# sensors.net
KiCad netlist of a schematic drawn in EAGLE
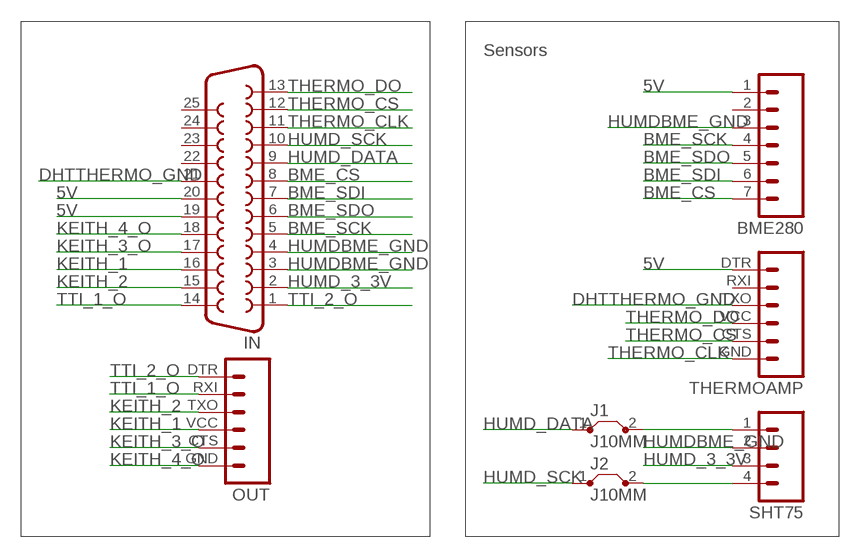
[diagram p0: schematic, sheet 1]

(export (version "E")
  (design (tool "Eeschema 10.0.6"))
  (components
    (comp (ref "BME280")
      (value "M07")
      (footprint "eagle-import:1X07")
      (libsource (lib "eagle-import") (part "M07"))
    )
    (comp (ref "IN")
      (value "F25HP")
      (footprint "eagle-import:F25HP")
      (libsource (lib "eagle-import") (part "F25HP"))
    )
    (comp (ref "J1")
      (value "J10MM")
      (footprint "eagle-import:10")
      (libsource (lib "eagle-import") (part "J10MM"))
    )
    (comp (ref "J2")
      (value "J10MM")
      (footprint "eagle-import:10")
      (libsource (lib "eagle-import") (part "J10MM"))
    )
    (comp (ref "OUT")
      (value "M06SIP")
      (footprint "eagle-import:1X06")
      (libsource (lib "eagle-import") (part "M06SIP"))
    )
    (comp (ref "SHT75")
      (value "M04SMD_LONG")
      (footprint "eagle-import:1X04-SMD_LONG")
      (libsource (lib "eagle-import") (part "M04SMD_LONG"))
    )
    (comp (ref "THERMOAMP")
      (value "M06SIP")
      (footprint "eagle-import:1X06")
      (libsource (lib "eagle-import") (part "M06SIP"))
    )
  )
  (nets
    (net (code "1") (name "/5V") (class "Default")
      (node (ref "BME280") (pin "1") (pinfunction "1_1") (pintype "passive"))
      (node (ref "IN") (pin "19") (pinfunction "19_19") (pintype "passive"))
      (node (ref "IN") (pin "20") (pinfunction "20_20") (pintype "passive"))
      (node (ref "THERMOAMP") (pin "DTR") (pinfunction "1_DTR") (pintype "passive"))
    )
    (net (code "2") (name "/BME_CS") (class "Default")
      (node (ref "BME280") (pin "7") (pinfunction "7_7") (pintype "passive"))
      (node (ref "IN") (pin "8") (pinfunction "8_8") (pintype "passive"))
    )
    (net (code "3") (name "/BME_SCK") (class "Default")
      (node (ref "BME280") (pin "4") (pinfunction "4_4") (pintype "passive"))
      (node (ref "IN") (pin "5") (pinfunction "5_5") (pintype "passive"))
    )
    (net (code "4") (name "/BME_SDI") (class "Default")
      (node (ref "BME280") (pin "6") (pinfunction "6_6") (pintype "passive"))
      (node (ref "IN") (pin "7") (pinfunction "7_7") (pintype "passive"))
    )
    (net (code "5") (name "/BME_SDO") (class "Default")
      (node (ref "BME280") (pin "5") (pinfunction "5_5") (pintype "passive"))
      (node (ref "IN") (pin "6") (pinfunction "6_6") (pintype "passive"))
    )
    (net (code "6") (name "/DHTTHERMO_GND") (class "Default")
      (node (ref "IN") (pin "21") (pinfunction "21_21") (pintype "passive"))
      (node (ref "THERMOAMP") (pin "TXO") (pinfunction "3_TXO") (pintype "passive"))
    )
    (net (code "7") (name "/HUMDBME_GND") (class "Default")
      (node (ref "BME280") (pin "3") (pinfunction "3_3") (pintype "passive"))
      (node (ref "IN") (pin "3") (pinfunction "3_3") (pintype "passive"))
      (node (ref "IN") (pin "4") (pinfunction "4_4") (pintype "passive"))
      (node (ref "SHT75") (pin "2") (pinfunction "2_2") (pintype "passive"))
    )
    (net (code "8") (name "/HUMD_3_3V") (class "Default")
      (node (ref "IN") (pin "2") (pinfunction "2_2") (pintype "passive"))
      (node (ref "SHT75") (pin "3") (pinfunction "3_3") (pintype "passive"))
    )
    (net (code "9") (name "/HUMD_DATA") (class "Default")
      (node (ref "IN") (pin "9") (pinfunction "9_9") (pintype "passive"))
      (node (ref "J1") (pin "1") (pinfunction "1_1") (pintype "passive"))
    )
    (net (code "10") (name "/HUMD_SCK") (class "Default")
      (node (ref "IN") (pin "10") (pinfunction "10_10") (pintype "passive"))
      (node (ref "J2") (pin "1") (pinfunction "1_1") (pintype "passive"))
    )
    (net (code "11") (name "/KEITH_1") (class "Default")
      (node (ref "IN") (pin "16") (pinfunction "16_16") (pintype "passive"))
      (node (ref "OUT") (pin "VCC") (pinfunction "4_VCC") (pintype "passive"))
    )
    (net (code "12") (name "/KEITH_2") (class "Default")
      (node (ref "IN") (pin "15") (pinfunction "15_15") (pintype "passive"))
      (node (ref "OUT") (pin "TXO") (pinfunction "3_TXO") (pintype "passive"))
    )
    (net (code "13") (name "/KEITH_3_O") (class "Default")
      (node (ref "IN") (pin "17") (pinfunction "17_17") (pintype "passive"))
      (node (ref "OUT") (pin "CTS") (pinfunction "5_CTS") (pintype "passive"))
    )
    (net (code "14") (name "/KEITH_4_O") (class "Default")
      (node (ref "IN") (pin "18") (pinfunction "18_18") (pintype "passive"))
      (node (ref "OUT") (pin "GND") (pinfunction "6_GND") (pintype "passive"))
    )
    (net (code "15") (name "/THERMO_CLK") (class "Default")
      (node (ref "IN") (pin "11") (pinfunction "11_11") (pintype "passive"))
      (node (ref "THERMOAMP") (pin "GND") (pinfunction "6_GND") (pintype "passive"))
    )
    (net (code "16") (name "/THERMO_CS") (class "Default")
      (node (ref "IN") (pin "12") (pinfunction "12_12") (pintype "passive"))
      (node (ref "THERMOAMP") (pin "CTS") (pinfunction "5_CTS") (pintype "passive"))
    )
    (net (code "17") (name "/THERMO_DO") (class "Default")
      (node (ref "IN") (pin "13") (pinfunction "13_13") (pintype "passive"))
      (node (ref "THERMOAMP") (pin "VCC") (pinfunction "4_VCC") (pintype "passive"))
    )
    (net (code "18") (name "/TTI_1_O") (class "Default")
      (node (ref "IN") (pin "14") (pinfunction "14_14") (pintype "passive"))
      (node (ref "OUT") (pin "RXI") (pinfunction "2_RXI") (pintype "passive"))
    )
    (net (code "19") (name "/TTI_2_O") (class "Default")
      (node (ref "IN") (pin "1") (pinfunction "1_1") (pintype "passive"))
      (node (ref "OUT") (pin "DTR") (pinfunction "1_DTR") (pintype "passive"))
    )
    (net (code "20") (name "Net-(J1-Pad2)") (class "Default")
      (node (ref "J1") (pin "2") (pinfunction "2_2") (pintype "passive"))
      (node (ref "SHT75") (pin "1") (pinfunction "1_1") (pintype "passive"))
    )
    (net (code "21") (name "Net-(J2-Pad2)") (class "Default")
      (node (ref "J2") (pin "2") (pinfunction "2_2") (pintype "passive"))
      (node (ref "SHT75") (pin "4") (pinfunction "4_4") (pintype "passive"))
    )
    (net (code "22") (name "unconnected-(BME280-Pad2)") (class "Default")
      (node (ref "BME280") (pin "2") (pinfunction "2_2") (pintype "passive"))
    )
    (net (code "23") (name "unconnected-(IN-Pad22)") (class "Default")
      (node (ref "IN") (pin "22") (pinfunction "22_22") (pintype "passive"))
    )
    (net (code "24") (name "unconnected-(IN-Pad23)") (class "Default")
      (node (ref "IN") (pin "23") (pinfunction "23_23") (pintype "passive"))
    )
    (net (code "25") (name "unconnected-(IN-Pad24)") (class "Default")
      (node (ref "IN") (pin "24") (pinfunction "24_24") (pintype "passive"))
    )
    (net (code "26") (name "unconnected-(IN-Pad25)") (class "Default")
      (node (ref "IN") (pin "25") (pinfunction "25_25") (pintype "passive"))
    )
    (net (code "27") (name "unconnected-(THERMOAMP-2-PadRXI)") (class "Default")
      (node (ref "THERMOAMP") (pin "RXI") (pinfunction "2_RXI") (pintype "passive"))
    )
  )
)
